# 02_ESP12.net
KiCad netlist of a schematic drawn in Altium Designer
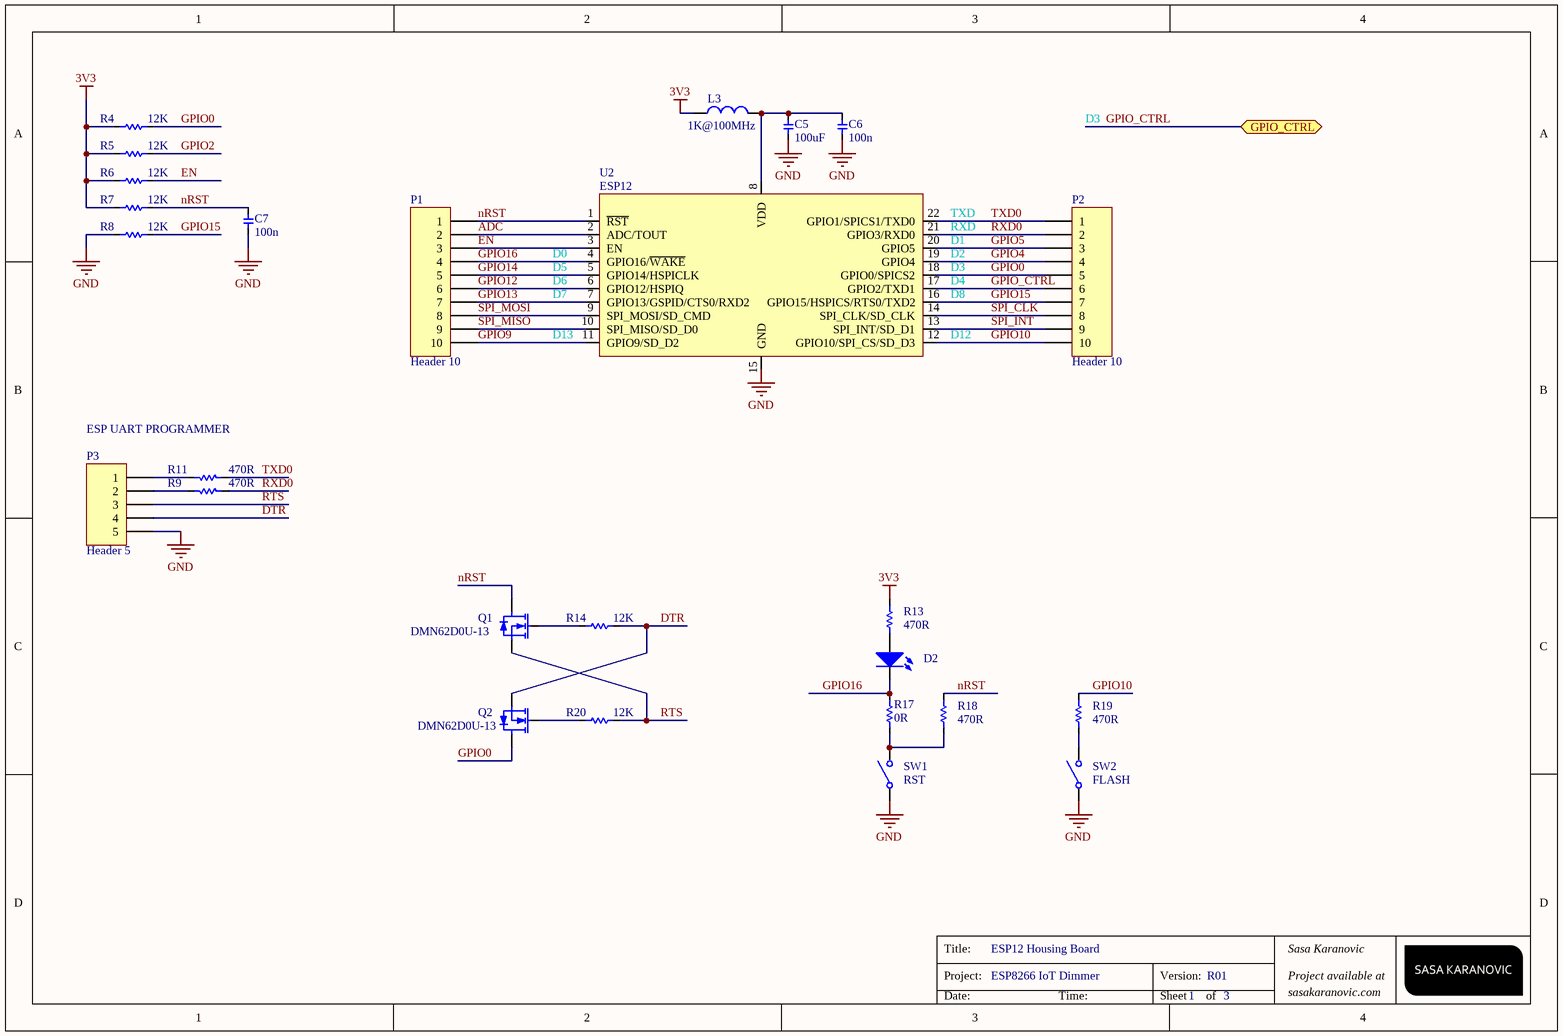
[diagram p0: 02_ESP12.SchDoc]

(export (version "E")
  (design (tool "Eeschema 10.0.6"))
  (components
    (comp (ref "C5")
      (value "100uF")
      (footprint "Moji Footprintovi:CAPC_1411_3528_X08N")
      (description "Capacitor")
      (fields
        (field (name "MANUFACTURER") "AVX Corporation")
        (field (name "MANUFACTURER PART NUMBER") "TAJB107M006RNJ")
      )
      (libsource (lib "Moji Schematici") (part "Cap"))
    )
    (comp (ref "C6")
      (value "100n")
      (footprint "Moji Footprintovi:0603 - CAP")
      (description "Capacitor")
      (fields
        (field (name "MANUFACTURER") "AVX Corporation")
        (field (name "MANUFACTURER PART NUMBER") "06035C104KAT2A")
      )
      (libsource (lib "Moji Schematici") (part "Cap"))
    )
    (comp (ref "C7")
      (value "100n")
      (footprint "Moji Footprintovi:0603 - CAP")
      (description "Capacitor")
      (fields
        (field (name "MANUFACTURER") "AVX Corporation")
        (field (name "MANUFACTURER PART NUMBER") "06035C104KAT2A")
      )
      (libsource (lib "Moji Schematici") (part "Cap"))
    )
    (comp (ref "D2")
      (value "LED")
      (footprint "Moji Footprintovi:0603 Diode")
      (description "Typical RED GaAs LED")
      (fields
        (field (name "DISTRIBUTOR PART NUMBER") "160-1830-1-ND")
        (field (name "MANUFACTURER") "Lite-On Inc.")
      )
      (libsource (lib "Moji Schematici") (part "LED"))
    )
    (comp (ref "L3")
      (value "1K@100MHz")
      (footprint "Moji Footprintovi:0603")
      (description "FERRITE BEAD 1 KOHM 0603 1LN")
      (fields
        (field (name "MANUFACTURER") "TDK Corporation")
        (field (name "MANUFACTURER PART NUMBER") "MPZ1608S102ATA00")
      )
      (libsource (lib "Moji Schematici") (part "Inductor"))
    )
    (comp (ref "P1")
      (value "Header 10")
      (footprint "HDR1X10")
      (description "Header, 10-Pin")
      (fields
        (field (name "DISTRIBUTOR PART NUMBER") "952-1843-ND")
        (field (name "MANUFACTURER") "Harwin Inc.")
      )
      (libsource (lib "") (part "Header 10_1"))
    )
    (comp (ref "P2")
      (value "Header 10")
      (footprint "HDR1X10")
      (description "Header, 10-Pin")
      (fields
        (field (name "DISTRIBUTOR PART NUMBER") "952-1843-ND")
        (field (name "MANUFACTURER") "Harwin Inc.")
      )
      (libsource (lib "Moji Schematici") (part "Header 10"))
    )
    (comp (ref "P3")
      (value "Header 5")
      (footprint "Moji Footprintovi:Header 5x1")
      (description "SIL VERTICAL PC TAIL PIN HEADER")
      (fields
        (field (name "MANUFACTURER") "Harwin Inc.")
        (field (name "MANUFACTURER PART NUMBER") "M20-9990546")
      )
      (libsource (lib "Moji Schematici") (part "Header 5"))
    )
    (comp (ref "Q1")
      (value "DMN62D0U-13")
      (footprint "Moji Footprintovi:SOT90P240X100-3N")
      (description "MOSFET N-CH 60V 0.38A")
      (fields
        (field (name "MANUFACTURER") "Diodes Incorporated")
        (field (name "DISTRIBUTOR PART NUMBER") "DMN62D0U-13DICT-ND")
      )
      (libsource (lib "Moji Schematici") (part "DMN62D0U-13"))
    )
    (comp (ref "Q2")
      (value "DMN62D0U-13")
      (footprint "Moji Footprintovi:SOT90P240X100-3N")
      (description "MOSFET N-CH 60V 0.38A")
      (fields
        (field (name "MANUFACTURER") "Diodes Incorporated")
        (field (name "DISTRIBUTOR PART NUMBER") "DMN62D0U-13DICT-ND")
      )
      (libsource (lib "Moji Schematici") (part "DMN62D0U-13"))
    )
    (comp (ref "R4")
      (value "12K")
      (footprint "Moji Footprintovi:0603")
      (description "Resistor")
      (fields
        (field (name "MANUFACTURER") "Yageo")
        (field (name "MANUFACTURER PART NUMBER") "RT0603FRE0712KL")
      )
      (libsource (lib "Moji Schematici") (part "Res"))
    )
    (comp (ref "R5")
      (value "12K")
      (footprint "Moji Footprintovi:0603")
      (description "Resistor")
      (fields
        (field (name "MANUFACTURER") "Yageo")
        (field (name "MANUFACTURER PART NUMBER") "RT0603FRE0712KL")
      )
      (libsource (lib "Moji Schematici") (part "Res"))
    )
    (comp (ref "R6")
      (value "12K")
      (footprint "Moji Footprintovi:0603")
      (description "Resistor")
      (fields
        (field (name "MANUFACTURER") "Yageo")
        (field (name "MANUFACTURER PART NUMBER") "RT0603FRE0712KL")
      )
      (libsource (lib "Moji Schematici") (part "Res"))
    )
    (comp (ref "R7")
      (value "12K")
      (footprint "Moji Footprintovi:0603")
      (description "Resistor")
      (fields
        (field (name "MANUFACTURER") "Yageo")
        (field (name "MANUFACTURER PART NUMBER") "RT0603FRE0712KL")
      )
      (libsource (lib "Moji Schematici") (part "Res"))
    )
    (comp (ref "R8")
      (value "12K")
      (footprint "Moji Footprintovi:0603")
      (description "Resistor")
      (fields
        (field (name "MANUFACTURER") "Yageo")
        (field (name "MANUFACTURER PART NUMBER") "RT0603FRE0712KL")
      )
      (libsource (lib "Moji Schematici") (part "Res"))
    )
    (comp (ref "R9")
      (value "470R")
      (footprint "Moji Footprintovi:0603")
      (description "Resistor")
      (fields
        (field (name "MANUFACTURER") "Yageo")
        (field (name "MANUFACTURER PART NUMBER") "AC0603FR-07470RL")
      )
      (libsource (lib "Moji Schematici") (part "Res"))
    )
    (comp (ref "R11")
      (value "470R")
      (footprint "Moji Footprintovi:0603")
      (description "Resistor")
      (fields
        (field (name "MANUFACTURER") "Yageo")
        (field (name "MANUFACTURER PART NUMBER") "AC0603FR-07470RL")
      )
      (libsource (lib "Moji Schematici") (part "Res"))
    )
    (comp (ref "R13")
      (value "470R")
      (footprint "Moji Footprintovi:0603")
      (description "Resistor")
      (fields
        (field (name "MANUFACTURER") "Yageo")
        (field (name "MANUFACTURER PART NUMBER") "AC0603FR-07470RL")
      )
      (libsource (lib "Moji Schematici") (part "Res"))
    )
    (comp (ref "R14")
      (value "12K")
      (footprint "Moji Footprintovi:0603")
      (description "Resistor")
      (fields
        (field (name "MANUFACTURER") "Yageo")
        (field (name "MANUFACTURER PART NUMBER") "RT0603FRE0712KL")
      )
      (libsource (lib "Moji Schematici") (part "Res"))
    )
    (comp (ref "R17")
      (value "0R")
      (footprint "Moji Footprintovi:0603")
      (description "Resistor")
      (fields
        (field (name "MANUFACTURER") "Yageo")
        (field (name "MANUFACTURER PART NUMBER") "RC0603JR-070RL")
      )
      (libsource (lib "Moji Schematici") (part "Res"))
    )
    (comp (ref "R18")
      (value "470R")
      (footprint "Moji Footprintovi:0603")
      (description "Resistor")
      (fields
        (field (name "MANUFACTURER") "Yageo")
        (field (name "MANUFACTURER PART NUMBER") "AC0603FR-07470RL")
      )
      (libsource (lib "Moji Schematici") (part "Res"))
    )
    (comp (ref "R19")
      (value "470R")
      (footprint "Moji Footprintovi:0603")
      (description "Resistor")
      (fields
        (field (name "MANUFACTURER") "Yageo")
        (field (name "MANUFACTURER PART NUMBER") "AC0603FR-07470RL")
      )
      (libsource (lib "Moji Schematici") (part "Res"))
    )
    (comp (ref "R20")
      (value "12K")
      (footprint "Moji Footprintovi:0603")
      (description "Resistor")
      (fields
        (field (name "MANUFACTURER") "Yageo")
        (field (name "MANUFACTURER PART NUMBER") "RT0603FRE0712KL")
      )
      (libsource (lib "Moji Schematici") (part "Res"))
    )
    (comp (ref "SW1")
      (value "Switch")
      (footprint "SMD Switch 2pin")
      (fields
        (field (name "DISTRIBUTOR PART NUMBER") "952-1843-ND")
        (field (name "MANUFACTURER") "Harwin Inc.")
        (field (name "MANUFACTURER PART NUMBER") "M20-9991046")
      )
      (libsource (lib "Moji Schematici") (part "Switch"))
    )
    (comp (ref "SW2")
      (value "Switch")
      (footprint "SMD Switch 2pin")
      (fields
        (field (name "DISTRIBUTOR PART NUMBER") "952-1843-ND")
        (field (name "MANUFACTURER") "Harwin Inc.")
        (field (name "MANUFACTURER PART NUMBER") "M20-9991046")
      )
      (libsource (lib "Moji Schematici") (part "Switch"))
    )
    (comp (ref "U2")
      (value "ESP12")
      (footprint "Moji Footprintovi:ESP-12")
      (description "ESP8266 SMT Module - ESP-12S")
      (fields
        (field (name "MANUFACTURER") "Seeed Technology Co., Ltd")
        (field (name "MANUFACTURER PART NUMBER") "317060015")
      )
      (libsource (lib "Moji Schematici") (part "ESP12"))
    )
  )
  (nets
    (net (code "1") (name "/ADC") (class "Default")
      (node (ref "P1") (pin "2") (pinfunction "2_2") (pintype "passive"))
      (node (ref "U2") (pin "2") (pinfunction "ADC/TOUT_2") (pintype "passive"))
    )
    (net (code "2") (name "/DTR") (class "Default")
      (node (ref "P3") (pin "4") (pinfunction "4_4") (pintype "passive"))
      (node (ref "Q2") (pin "3") (pinfunction "S_3") (pintype "passive"))
      (node (ref "R14") (pin "2") (pinfunction "2_2") (pintype "passive"))
    )
    (net (code "3") (name "/EN") (class "Default")
      (node (ref "P1") (pin "3") (pinfunction "3_3") (pintype "passive"))
      (node (ref "R6") (pin "2") (pinfunction "2_2") (pintype "passive"))
      (node (ref "U2") (pin "3") (pinfunction "EN_3") (pintype "passive"))
    )
    (net (code "4") (name "/GPIO0") (class "Default")
      (node (ref "P2") (pin "5") (pinfunction "5_5") (pintype "passive"))
      (node (ref "Q2") (pin "2") (pinfunction "D_2") (pintype "passive"))
      (node (ref "R4") (pin "2") (pinfunction "2_2") (pintype "passive"))
      (node (ref "U2") (pin "18") (pinfunction "GPIO0/SPICS2_18") (pintype "passive"))
    )
    (net (code "5") (name "/GPIO2") (class "Default")
      (node (ref "R5") (pin "2") (pinfunction "2_2") (pintype "passive"))
    )
    (net (code "6") (name "/GPIO4") (class "Default")
      (node (ref "P2") (pin "4") (pinfunction "4_4") (pintype "passive"))
      (node (ref "U2") (pin "19") (pinfunction "GPIO4_19") (pintype "passive"))
    )
    (net (code "7") (name "/GPIO5") (class "Default")
      (node (ref "P2") (pin "3") (pinfunction "3_3") (pintype "passive"))
      (node (ref "U2") (pin "20") (pinfunction "GPIO5_20") (pintype "passive"))
    )
    (net (code "8") (name "/GPIO9") (class "Default")
      (node (ref "P1") (pin "10") (pinfunction "10_10") (pintype "passive"))
      (node (ref "U2") (pin "11") (pinfunction "GPIO9/SD_D2_11") (pintype "passive"))
    )
    (net (code "9") (name "/GPIO10") (class "Default")
      (node (ref "P2") (pin "10") (pinfunction "10_10") (pintype "passive"))
      (node (ref "R19") (pin "2") (pinfunction "2_2") (pintype "passive"))
      (node (ref "U2") (pin "12") (pinfunction "GPIO10/SPI_CS/SD_D3_12") (pintype "passive"))
    )
    (net (code "10") (name "/GPIO12") (class "Default")
      (node (ref "P1") (pin "6") (pinfunction "6_6") (pintype "passive"))
      (node (ref "U2") (pin "6") (pinfunction "GPIO12/HSPIQ_6") (pintype "passive"))
    )
    (net (code "11") (name "/GPIO13") (class "Default")
      (node (ref "P1") (pin "7") (pinfunction "7_7") (pintype "passive"))
      (node (ref "U2") (pin "7") (pinfunction "GPIO13/GSPID/CTS0/RXD2_7") (pintype "passive"))
    )
    (net (code "12") (name "/GPIO14") (class "Default")
      (node (ref "P1") (pin "5") (pinfunction "5_5") (pintype "passive"))
      (node (ref "U2") (pin "5") (pinfunction "GPIO14/HSPICLK_5") (pintype "passive"))
    )
    (net (code "13") (name "/GPIO15") (class "Default")
      (node (ref "P2") (pin "7") (pinfunction "7_7") (pintype "passive"))
      (node (ref "R8") (pin "2") (pinfunction "2_2") (pintype "passive"))
      (node (ref "U2") (pin "16") (pinfunction "GPIO15/HSPICS/RTS0/TXD2_16") (pintype "passive"))
    )
    (net (code "14") (name "/GPIO16") (class "Default")
      (node (ref "D2") (pin "K") (pinfunction "K_K") (pintype "passive"))
      (node (ref "P1") (pin "4") (pinfunction "4_4") (pintype "passive"))
      (node (ref "R17") (pin "1") (pinfunction "1_1") (pintype "passive"))
      (node (ref "U2") (pin "4") (pinfunction "GPIO16/~{WAKE}_4") (pintype "passive"))
    )
    (net (code "15") (name "/GPIO_CTRL") (class "Default")
      (node (ref "P2") (pin "6") (pinfunction "6_6") (pintype "passive"))
      (node (ref "U2") (pin "17") (pinfunction "GPIO2/TXD1_17") (pintype "passive"))
    )
    (net (code "16") (name "/RTS") (class "Default")
      (node (ref "P3") (pin "3") (pinfunction "3_3") (pintype "passive"))
      (node (ref "Q1") (pin "3") (pinfunction "S_3") (pintype "passive"))
      (node (ref "R20") (pin "2") (pinfunction "2_2") (pintype "passive"))
    )
    (net (code "17") (name "/RXD0") (class "Default")
      (node (ref "P2") (pin "2") (pinfunction "2_2") (pintype "passive"))
      (node (ref "R9") (pin "2") (pinfunction "2_2") (pintype "passive"))
      (node (ref "U2") (pin "21") (pinfunction "GPIO3/RXD0_21") (pintype "passive"))
    )
    (net (code "18") (name "/SPI_CLK") (class "Default")
      (node (ref "P2") (pin "8") (pinfunction "8_8") (pintype "passive"))
      (node (ref "U2") (pin "14") (pinfunction "SPI_CLK/SD_CLK_14") (pintype "passive"))
    )
    (net (code "19") (name "/SPI_INT") (class "Default")
      (node (ref "P2") (pin "9") (pinfunction "9_9") (pintype "passive"))
      (node (ref "U2") (pin "13") (pinfunction "SPI_INT/SD_D1_13") (pintype "passive"))
    )
    (net (code "20") (name "/SPI_MISO") (class "Default")
      (node (ref "P1") (pin "9") (pinfunction "9_9") (pintype "passive"))
      (node (ref "U2") (pin "10") (pinfunction "SPI_MISO/SD_D0_10") (pintype "passive"))
    )
    (net (code "21") (name "/SPI_MOSI") (class "Default")
      (node (ref "P1") (pin "8") (pinfunction "8_8") (pintype "passive"))
      (node (ref "U2") (pin "9") (pinfunction "SPI_MOSI/SD_CMD_9") (pintype "passive"))
    )
    (net (code "22") (name "/TXD0") (class "Default")
      (node (ref "P2") (pin "1") (pinfunction "1_1") (pintype "passive"))
      (node (ref "R11") (pin "2") (pinfunction "2_2") (pintype "passive"))
      (node (ref "U2") (pin "22") (pinfunction "GPIO1/SPICS1/TXD0_22") (pintype "passive"))
    )
    (net (code "23") (name "/nRST") (class "Default")
      (node (ref "C7") (pin "2") (pinfunction "2_2") (pintype "passive"))
      (node (ref "P1") (pin "1") (pinfunction "1_1") (pintype "passive"))
      (node (ref "Q1") (pin "2") (pinfunction "D_2") (pintype "passive"))
      (node (ref "R18") (pin "2") (pinfunction "2_2") (pintype "passive"))
      (node (ref "R7") (pin "2") (pinfunction "2_2") (pintype "passive"))
      (node (ref "U2") (pin "1") (pinfunction "~{RST}_1") (pintype "passive"))
    )
    (net (code "24") (name "3V3") (class "Default")
      (node (ref "L3") (pin "1") (pinfunction "1_1") (pintype "passive"))
      (node (ref "R13") (pin "2") (pinfunction "2_2") (pintype "passive"))
      (node (ref "R4") (pin "1") (pinfunction "1_1") (pintype "passive"))
      (node (ref "R5") (pin "1") (pinfunction "1_1") (pintype "passive"))
      (node (ref "R6") (pin "1") (pinfunction "1_1") (pintype "passive"))
      (node (ref "R7") (pin "1") (pinfunction "1_1") (pintype "passive"))
    )
    (net (code "25") (name "GND") (class "Default")
      (node (ref "C5") (pin "1") (pinfunction "1_1") (pintype "passive"))
      (node (ref "C6") (pin "1") (pinfunction "1_1") (pintype "passive"))
      (node (ref "C7") (pin "1") (pinfunction "1_1") (pintype "passive"))
      (node (ref "P3") (pin "5") (pinfunction "5_5") (pintype "passive"))
      (node (ref "R8") (pin "1") (pinfunction "1_1") (pintype "passive"))
      (node (ref "SW1") (pin "1") (pinfunction "COMMON1_1") (pintype "passive"))
      (node (ref "SW2") (pin "1") (pinfunction "COMMON1_1") (pintype "passive"))
      (node (ref "U2") (pin "15") (pinfunction "GND_15") (pintype "passive"))
    )
    (net (code "26") (name "Net-(D2-PadA)") (class "Default")
      (node (ref "D2") (pin "A") (pinfunction "A_A") (pintype "passive"))
      (node (ref "R13") (pin "1") (pinfunction "1_1") (pintype "passive"))
    )
    (net (code "27") (name "Net-(P3-Pad1)") (class "Default")
      (node (ref "P3") (pin "1") (pinfunction "1_1") (pintype "passive"))
      (node (ref "R11") (pin "1") (pinfunction "1_1") (pintype "passive"))
    )
    (net (code "28") (name "Net-(P3-Pad2)") (class "Default")
      (node (ref "P3") (pin "2") (pinfunction "2_2") (pintype "passive"))
      (node (ref "R9") (pin "1") (pinfunction "1_1") (pintype "passive"))
    )
    (net (code "29") (name "Net-(Q1-G)") (class "Default")
      (node (ref "Q1") (pin "1") (pinfunction "G_1") (pintype "passive"))
      (node (ref "R14") (pin "1") (pinfunction "1_1") (pintype "passive"))
    )
    (net (code "30") (name "Net-(Q2-G)") (class "Default")
      (node (ref "Q2") (pin "1") (pinfunction "G_1") (pintype "passive"))
      (node (ref "R20") (pin "1") (pinfunction "1_1") (pintype "passive"))
    )
    (net (code "31") (name "Net-(SW1-COMMON2)") (class "Default")
      (node (ref "R17") (pin "2") (pinfunction "2_2") (pintype "passive"))
      (node (ref "R18") (pin "1") (pinfunction "1_1") (pintype "passive"))
      (node (ref "SW1") (pin "2") (pinfunction "COMMON2_2") (pintype "passive"))
    )
    (net (code "32") (name "Net-(SW2-COMMON2)") (class "Default")
      (node (ref "R19") (pin "1") (pinfunction "1_1") (pintype "passive"))
      (node (ref "SW2") (pin "2") (pinfunction "COMMON2_2") (pintype "passive"))
    )
    (net (code "33") (name "Net-(U2-VDD)") (class "Default")
      (node (ref "C5") (pin "2") (pinfunction "2_2") (pintype "passive"))
      (node (ref "C6") (pin "2") (pinfunction "2_2") (pintype "passive"))
      (node (ref "L3") (pin "2") (pinfunction "2_2") (pintype "passive"))
      (node (ref "U2") (pin "8") (pinfunction "VDD_8") (pintype "passive"))
    )
  )
)
